# Pro-Micro-v11.net
KiCad netlist of a schematic drawn in EAGLE
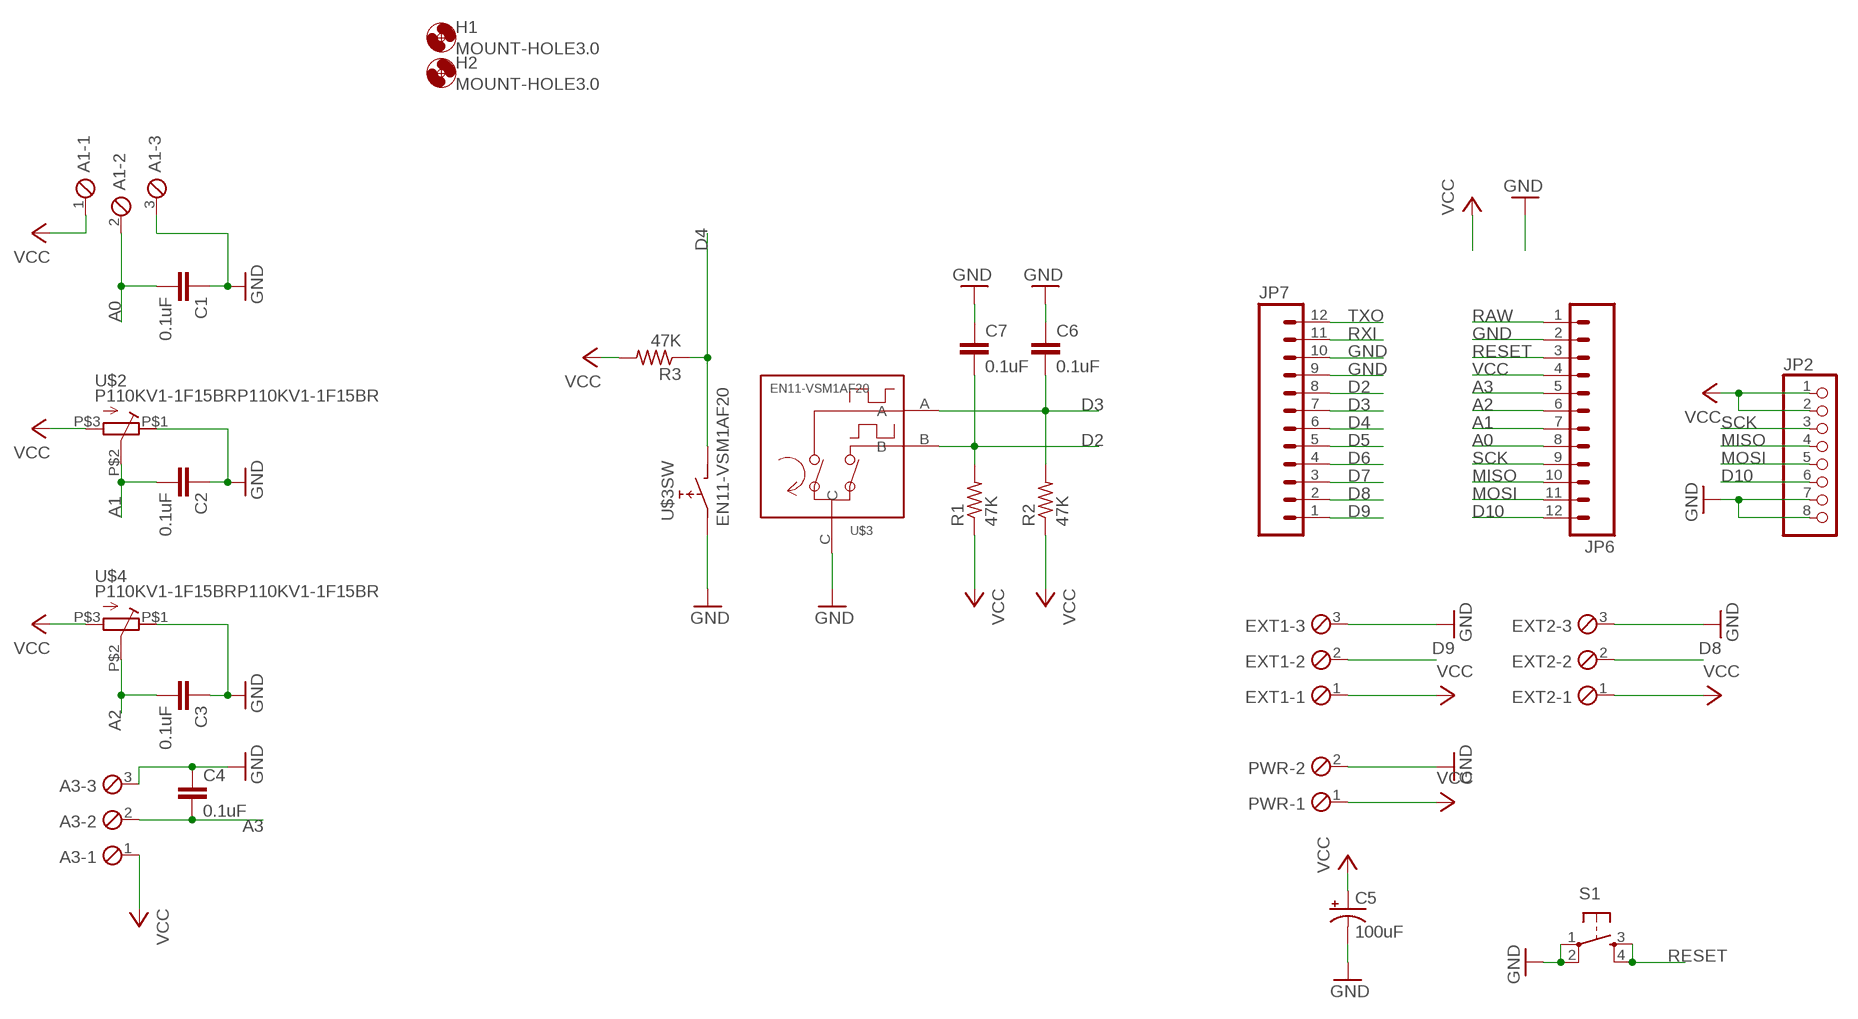
[diagram p0: schematic, sheet 1]

(export (version "E")
  (design (tool "Eeschema 10.0.6"))
  (components
    (comp (ref "A1")
      (value "MPT3")
      (footprint "eagle-import:3POL254")
      (libsource (lib "eagle-import") (part "MPT3"))
    )
    (comp (ref "A3")
      (value "MPT3")
      (footprint "eagle-import:3POL254")
      (libsource (lib "eagle-import") (part "MPT3"))
    )
    (comp (ref "C1")
      (value "0.1uF")
      (footprint "eagle-import:C025-025X050")
      (libsource (lib "eagle-import") (part "C-EU025-025X050"))
    )
    (comp (ref "C2")
      (value "0.1uF")
      (footprint "eagle-import:C025-025X050")
      (libsource (lib "eagle-import") (part "C-EU025-025X050"))
    )
    (comp (ref "C3")
      (value "0.1uF")
      (footprint "eagle-import:C025-025X050")
      (libsource (lib "eagle-import") (part "C-EU025-025X050"))
    )
    (comp (ref "C4")
      (value "0.1uF")
      (footprint "eagle-import:C025-025X050")
      (libsource (lib "eagle-import") (part "C-EU025-025X050"))
    )
    (comp (ref "C5")
      (value "100uF")
      (footprint "eagle-import:E3,5-8")
      (libsource (lib "eagle-import") (part "CPOL-USE3.5-8"))
    )
    (comp (ref "C6")
      (value "0.1uF")
      (footprint "eagle-import:C025-024X044")
      (libsource (lib "eagle-import") (part "C-EU025-024X044"))
    )
    (comp (ref "C7")
      (value "0.1uF")
      (footprint "eagle-import:C025-024X044")
      (libsource (lib "eagle-import") (part "C-EU025-024X044"))
    )
    (comp (ref "EXT1")
      (value "MPT3")
      (footprint "eagle-import:3POL254")
      (libsource (lib "eagle-import") (part "MPT3"))
    )
    (comp (ref "EXT2")
      (value "MPT3")
      (footprint "eagle-import:3POL254")
      (libsource (lib "eagle-import") (part "MPT3"))
    )
    (comp (ref "H1")
      (value "MOUNT-HOLE3.0")
      (footprint "eagle-import:3,0")
      (libsource (lib "eagle-import") (part "MOUNT-HOLE3.0"))
    )
    (comp (ref "H2")
      (value "MOUNT-HOLE3.0")
      (footprint "eagle-import:3,0")
      (libsource (lib "eagle-import") (part "MOUNT-HOLE3.0"))
    )
    (comp (ref "JP2")
      (value "HEADER-1X8")
      (footprint "eagle-import:1X08_OVAL")
      (libsource (lib "eagle-import") (part "HEADER-1X8"))
    )
    (comp (ref "JP6")
      (value "M12PTH")
      (footprint "eagle-import:1X12")
      (libsource (lib "eagle-import") (part "M12PTH"))
    )
    (comp (ref "JP7")
      (value "M12PTH")
      (footprint "eagle-import:1X12")
      (libsource (lib "eagle-import") (part "M12PTH"))
    )
    (comp (ref "PWR")
      (value "MPT2")
      (footprint "eagle-import:2POL254")
      (libsource (lib "eagle-import") (part "MPT2"))
    )
    (comp (ref "R1")
      (value "47K")
      (footprint "eagle-import:0204_5")
      (libsource (lib "eagle-import") (part "R-US_0204/5"))
    )
    (comp (ref "R2")
      (value "47K")
      (footprint "eagle-import:0204_5")
      (libsource (lib "eagle-import") (part "R-US_0204/5"))
    )
    (comp (ref "R3")
      (value "47K")
      (footprint "eagle-import:0204_5")
      (libsource (lib "eagle-import") (part "R-US_0204/5"))
    )
    (comp (ref "S1")
      (value "TAC_SWITCHPTH")
      (footprint "eagle-import:TACTILE-PTH")
      (libsource (lib "eagle-import") (part "TAC_SWITCHPTH"))
    )
    (comp (ref "U$2")
      (value "P110KV1-1F15BRP110KV1-1F15BR")
      (footprint "eagle-import:P110KV1-1F15BR")
      (libsource (lib "eagle-import") (part "P110KV1-1F15BRP110KV1-1F15BR"))
    )
    (comp (ref "U$3")
      (value "EN11-VSM1AF20")
      (footprint "eagle-import:EN11-VS_")
      (libsource (lib "eagle-import") (part "EN11"))
    )
    (comp (ref "U$4")
      (value "P110KV1-1F15BRP110KV1-1F15BR")
      (footprint "eagle-import:P110KV1-1F15BR")
      (libsource (lib "eagle-import") (part "P110KV1-1F15BRP110KV1-1F15BR"))
    )
  )
  (nets
    (net (code "1") (name "/A0") (class "Default")
      (node (ref "A1") (pin "2") (pinfunction "1_2") (pintype "passive"))
      (node (ref "C1") (pin "2") (pinfunction "2_2") (pintype "passive"))
      (node (ref "JP6") (pin "8") (pinfunction "8_8") (pintype "passive"))
    )
    (net (code "2") (name "/A1") (class "Default")
      (node (ref "C2") (pin "2") (pinfunction "2_2") (pintype "passive"))
      (node (ref "JP6") (pin "7") (pinfunction "7_7") (pintype "passive"))
      (node (ref "U$2") (pin "P$2") (pinfunction "S_P$2") (pintype "passive"))
    )
    (net (code "3") (name "/A2") (class "Default")
      (node (ref "C3") (pin "2") (pinfunction "2_2") (pintype "passive"))
      (node (ref "JP6") (pin "6") (pinfunction "6_6") (pintype "passive"))
      (node (ref "U$4") (pin "P$2") (pinfunction "S_P$2") (pintype "passive"))
    )
    (net (code "4") (name "/A3") (class "Default")
      (node (ref "A3") (pin "2") (pinfunction "1_2") (pintype "passive"))
      (node (ref "C4") (pin "2") (pinfunction "2_2") (pintype "passive"))
      (node (ref "JP6") (pin "5") (pinfunction "5_5") (pintype "passive"))
    )
    (net (code "5") (name "/D2") (class "Default")
      (node (ref "C7") (pin "2") (pinfunction "2_2") (pintype "passive"))
      (node (ref "JP7") (pin "8") (pinfunction "8_8") (pintype "passive"))
      (node (ref "R1") (pin "2") (pinfunction "2_2") (pintype "passive"))
      (node (ref "U$3") (pin "B") (pinfunction "B_B") (pintype "bidirectional"))
    )
    (net (code "6") (name "/D3") (class "Default")
      (node (ref "C6") (pin "2") (pinfunction "2_2") (pintype "passive"))
      (node (ref "JP7") (pin "7") (pinfunction "7_7") (pintype "passive"))
      (node (ref "R2") (pin "2") (pinfunction "2_2") (pintype "passive"))
      (node (ref "U$3") (pin "A") (pinfunction "A_A") (pintype "bidirectional"))
    )
    (net (code "7") (name "/D4") (class "Default")
      (node (ref "JP7") (pin "6") (pinfunction "6_6") (pintype "passive"))
      (node (ref "R3") (pin "1") (pinfunction "1_1") (pintype "passive"))
      (node (ref "U$3") (pin "E") (pinfunction "E_E") (pintype "passive"))
    )
    (net (code "8") (name "/D5") (class "Default")
      (node (ref "JP7") (pin "5") (pinfunction "5_5") (pintype "passive"))
    )
    (net (code "9") (name "/D6") (class "Default")
      (node (ref "JP7") (pin "4") (pinfunction "4_4") (pintype "passive"))
    )
    (net (code "10") (name "/D7") (class "Default")
      (node (ref "JP7") (pin "3") (pinfunction "3_3") (pintype "passive"))
    )
    (net (code "11") (name "/D8") (class "Default")
      (node (ref "EXT2") (pin "2") (pinfunction "1_2") (pintype "passive"))
      (node (ref "JP7") (pin "2") (pinfunction "2_2") (pintype "passive"))
    )
    (net (code "12") (name "/D9") (class "Default")
      (node (ref "EXT1") (pin "2") (pinfunction "1_2") (pintype "passive"))
      (node (ref "JP7") (pin "1") (pinfunction "1_1") (pintype "passive"))
    )
    (net (code "13") (name "/D10") (class "Default")
      (node (ref "JP2") (pin "6") (pinfunction "6_6") (pintype "passive"))
      (node (ref "JP6") (pin "12") (pinfunction "12_12") (pintype "passive"))
    )
    (net (code "14") (name "/MISO") (class "Default")
      (node (ref "JP2") (pin "4") (pinfunction "4_4") (pintype "passive"))
      (node (ref "JP6") (pin "10") (pinfunction "10_10") (pintype "passive"))
    )
    (net (code "15") (name "/MOSI") (class "Default")
      (node (ref "JP2") (pin "5") (pinfunction "5_5") (pintype "passive"))
      (node (ref "JP6") (pin "11") (pinfunction "11_11") (pintype "passive"))
    )
    (net (code "16") (name "/RAW") (class "Default")
      (node (ref "JP6") (pin "1") (pinfunction "1_1") (pintype "passive"))
    )
    (net (code "17") (name "/RESET") (class "Default")
      (node (ref "JP6") (pin "3") (pinfunction "3_3") (pintype "passive"))
      (node (ref "S1") (pin "3") (pinfunction "3_3") (pintype "passive"))
      (node (ref "S1") (pin "4") (pinfunction "4_4") (pintype "passive"))
    )
    (net (code "18") (name "/RXI") (class "Default")
      (node (ref "JP7") (pin "11") (pinfunction "11_11") (pintype "passive"))
    )
    (net (code "19") (name "/SCK") (class "Default")
      (node (ref "JP2") (pin "3") (pinfunction "3_3") (pintype "passive"))
      (node (ref "JP6") (pin "9") (pinfunction "9_9") (pintype "passive"))
    )
    (net (code "20") (name "/TXO") (class "Default")
      (node (ref "JP7") (pin "12") (pinfunction "12_12") (pintype "passive"))
    )
    (net (code "21") (name "GND") (class "Default")
      (node (ref "A1") (pin "3") (pinfunction "1_3") (pintype "passive"))
      (node (ref "A3") (pin "3") (pinfunction "1_3") (pintype "passive"))
      (node (ref "C1") (pin "1") (pinfunction "1_1") (pintype "passive"))
      (node (ref "C2") (pin "1") (pinfunction "1_1") (pintype "passive"))
      (node (ref "C3") (pin "1") (pinfunction "1_1") (pintype "passive"))
      (node (ref "C4") (pin "1") (pinfunction "1_1") (pintype "passive"))
      (node (ref "C5") (pin "-") (pinfunction "-_-") (pintype "passive"))
      (node (ref "C6") (pin "1") (pinfunction "1_1") (pintype "passive"))
      (node (ref "C7") (pin "1") (pinfunction "1_1") (pintype "passive"))
      (node (ref "EXT1") (pin "3") (pinfunction "1_3") (pintype "passive"))
      (node (ref "EXT2") (pin "3") (pinfunction "1_3") (pintype "passive"))
      (node (ref "JP2") (pin "7") (pinfunction "7_7") (pintype "passive"))
      (node (ref "JP2") (pin "8") (pinfunction "8_8") (pintype "passive"))
      (node (ref "JP6") (pin "2") (pinfunction "2_2") (pintype "passive"))
      (node (ref "JP7") (pin "10") (pinfunction "10_10") (pintype "passive"))
      (node (ref "JP7") (pin "9") (pinfunction "9_9") (pintype "passive"))
      (node (ref "PWR") (pin "2") (pinfunction "1_2") (pintype "passive"))
      (node (ref "S1") (pin "1") (pinfunction "1_1") (pintype "passive"))
      (node (ref "S1") (pin "2") (pinfunction "2_2") (pintype "passive"))
      (node (ref "U$2") (pin "P$1") (pinfunction "A_P$1") (pintype "passive"))
      (node (ref "U$3") (pin "C") (pinfunction "C_C") (pintype "bidirectional"))
      (node (ref "U$3") (pin "D") (pinfunction "D_D") (pintype "passive"))
      (node (ref "U$4") (pin "P$1") (pinfunction "A_P$1") (pintype "passive"))
    )
    (net (code "22") (name "VCC") (class "Default")
      (node (ref "A1") (pin "1") (pinfunction "1_1") (pintype "passive"))
      (node (ref "A3") (pin "1") (pinfunction "1_1") (pintype "passive"))
      (node (ref "C5") (pin "+") (pinfunction "+_+") (pintype "passive"))
      (node (ref "EXT1") (pin "1") (pinfunction "1_1") (pintype "passive"))
      (node (ref "EXT2") (pin "1") (pinfunction "1_1") (pintype "passive"))
      (node (ref "JP2") (pin "1") (pinfunction "1_1") (pintype "passive"))
      (node (ref "JP2") (pin "2") (pinfunction "2_2") (pintype "passive"))
      (node (ref "JP6") (pin "4") (pinfunction "4_4") (pintype "passive"))
      (node (ref "PWR") (pin "1") (pinfunction "1_1") (pintype "passive"))
      (node (ref "R1") (pin "1") (pinfunction "1_1") (pintype "passive"))
      (node (ref "R2") (pin "1") (pinfunction "1_1") (pintype "passive"))
      (node (ref "R3") (pin "2") (pinfunction "2_2") (pintype "passive"))
      (node (ref "U$2") (pin "P$3") (pinfunction "E_P$3") (pintype "passive"))
      (node (ref "U$4") (pin "P$3") (pinfunction "E_P$3") (pintype "passive"))
    )
  )
)
